# Filter6.net
KiCad netlist of a schematic drawn in Altium Designer
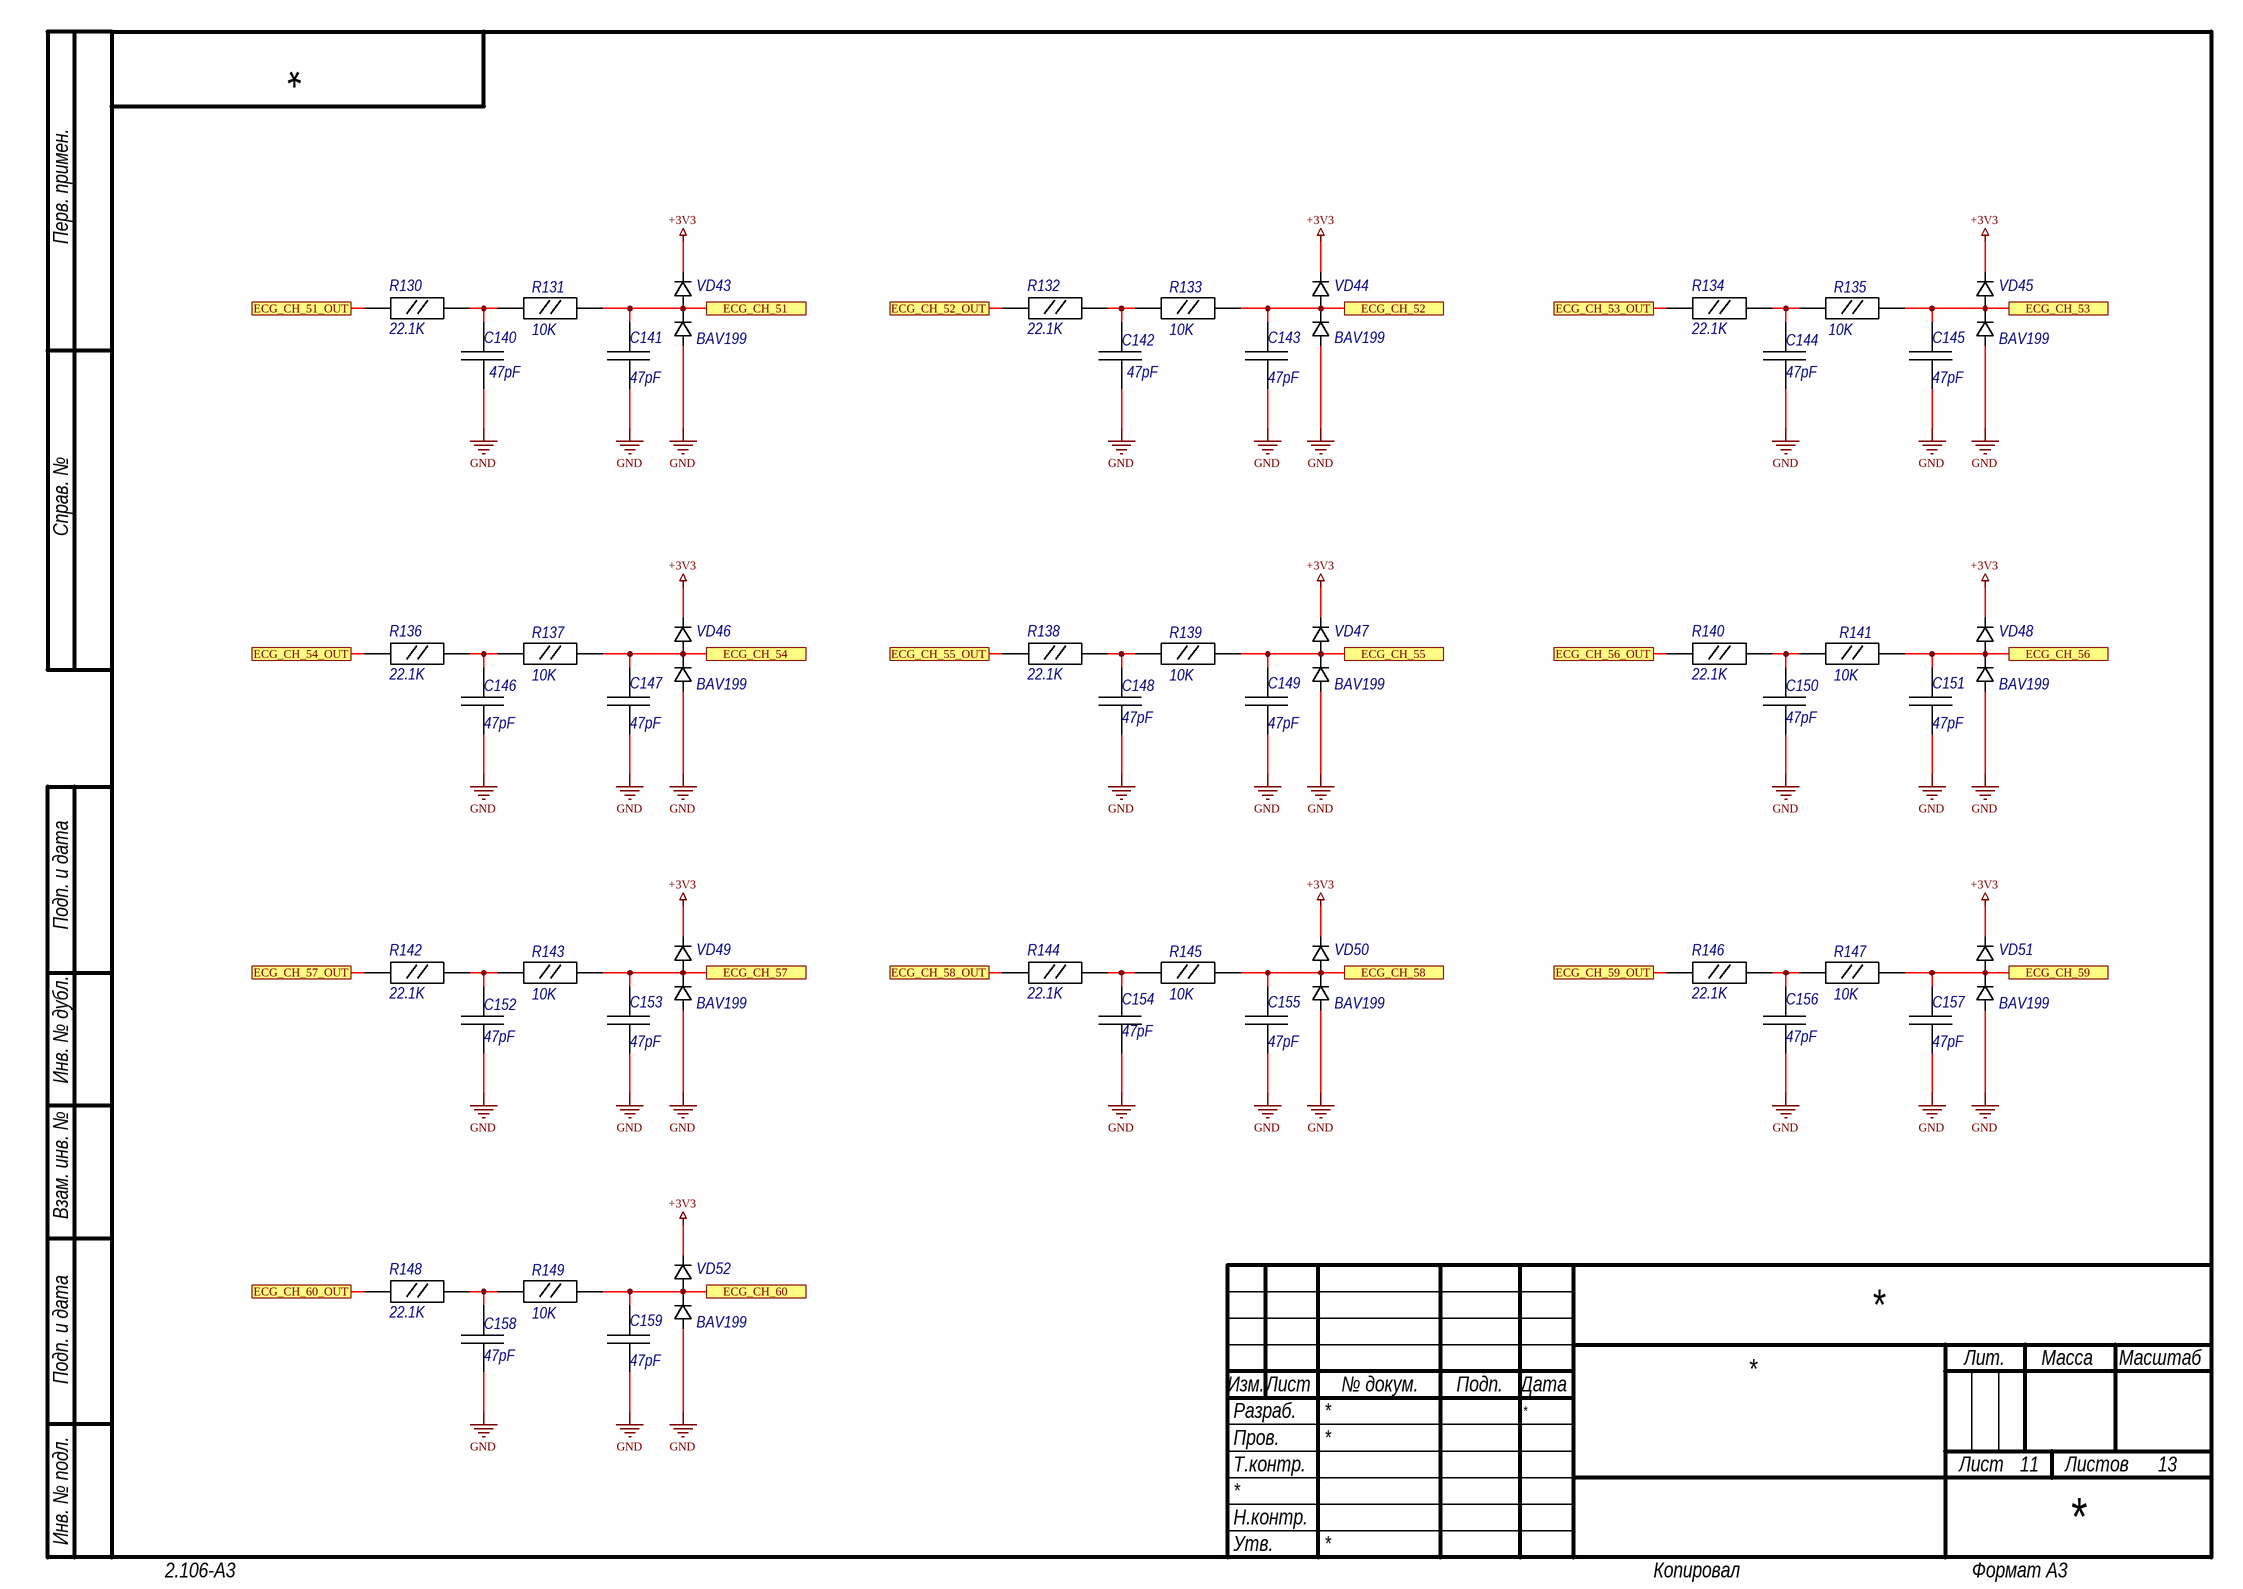
[diagram p0: Filter6.SchDoc]

(export (version "E")
  (design (tool "Eeschema 10.0.6"))
  (components
    (comp (ref "C140")
      (value "47pF")
      (footprint "C0603")
      (description "Ceramic Capacitor SMD")
      (libsource (lib "GOST") (part "CC_SMD_0603"))
    )
    (comp (ref "C141")
      (value "47pF")
      (footprint "C0603")
      (description "Ceramic Capacitor SMD")
      (libsource (lib "GOST") (part "CC_SMD_0603"))
    )
    (comp (ref "C142")
      (value "47pF")
      (footprint "C0603")
      (description "Ceramic Capacitor SMD")
      (libsource (lib "GOST") (part "CC_SMD_0603"))
    )
    (comp (ref "C143")
      (value "47pF")
      (footprint "C0603")
      (description "Ceramic Capacitor SMD")
      (libsource (lib "GOST") (part "CC_SMD_0603"))
    )
    (comp (ref "C144")
      (value "47pF")
      (footprint "C0603")
      (description "Ceramic Capacitor SMD")
      (libsource (lib "GOST") (part "CC_SMD_0603"))
    )
    (comp (ref "C145")
      (value "47pF")
      (footprint "C0603")
      (description "Ceramic Capacitor SMD")
      (libsource (lib "GOST") (part "CC_SMD_0603"))
    )
    (comp (ref "C146")
      (value "47pF")
      (footprint "C0603")
      (description "Ceramic Capacitor SMD")
      (libsource (lib "GOST") (part "CC_SMD_0603"))
    )
    (comp (ref "C147")
      (value "47pF")
      (footprint "C0603")
      (description "Ceramic Capacitor SMD")
      (libsource (lib "GOST") (part "CC_SMD_0603"))
    )
    (comp (ref "C148")
      (value "47pF")
      (footprint "C0603")
      (description "Ceramic Capacitor SMD")
      (libsource (lib "GOST") (part "CC_SMD_0603"))
    )
    (comp (ref "C149")
      (value "47pF")
      (footprint "C0603")
      (description "Ceramic Capacitor SMD")
      (libsource (lib "GOST") (part "CC_SMD_0603"))
    )
    (comp (ref "C150")
      (value "47pF")
      (footprint "C0603")
      (description "Ceramic Capacitor SMD")
      (libsource (lib "GOST") (part "CC_SMD_0603"))
    )
    (comp (ref "C151")
      (value "47pF")
      (footprint "C0603")
      (description "Ceramic Capacitor SMD")
      (libsource (lib "GOST") (part "CC_SMD_0603"))
    )
    (comp (ref "C152")
      (value "47pF")
      (footprint "C0603")
      (description "Ceramic Capacitor SMD")
      (libsource (lib "GOST") (part "CC_SMD_0603"))
    )
    (comp (ref "C153")
      (value "47pF")
      (footprint "C0603")
      (description "Ceramic Capacitor SMD")
      (libsource (lib "GOST") (part "CC_SMD_0603"))
    )
    (comp (ref "C154")
      (value "47pF")
      (footprint "C0603")
      (description "Ceramic Capacitor SMD")
      (libsource (lib "GOST") (part "CC_SMD_0603"))
    )
    (comp (ref "C155")
      (value "47pF")
      (footprint "C0603")
      (description "Ceramic Capacitor SMD")
      (libsource (lib "GOST") (part "CC_SMD_0603"))
    )
    (comp (ref "C156")
      (value "47pF")
      (footprint "C0603")
      (description "Ceramic Capacitor SMD")
      (libsource (lib "GOST") (part "CC_SMD_0603"))
    )
    (comp (ref "C157")
      (value "47pF")
      (footprint "C0603")
      (description "Ceramic Capacitor SMD")
      (libsource (lib "GOST") (part "CC_SMD_0603"))
    )
    (comp (ref "C158")
      (value "47pF")
      (footprint "C0603")
      (description "Ceramic Capacitor SMD")
      (libsource (lib "GOST") (part "CC_SMD_0603"))
    )
    (comp (ref "C159")
      (value "47pF")
      (footprint "C0603")
      (description "Ceramic Capacitor SMD")
      (libsource (lib "GOST") (part "CC_SMD_0603"))
    )
    (comp (ref "R130")
      (value "22.1K")
      (footprint "R0603")
      (description "Resistor SMD")
      (libsource (lib "GOST") (part "R0603"))
    )
    (comp (ref "R131")
      (value "10K")
      (footprint "R0603")
      (description "Resistor SMD")
      (libsource (lib "GOST") (part "R0603"))
    )
    (comp (ref "R132")
      (value "22.1K")
      (footprint "R0603")
      (description "Resistor SMD")
      (libsource (lib "GOST") (part "R0603"))
    )
    (comp (ref "R133")
      (value "10K")
      (footprint "R0603")
      (description "Resistor SMD")
      (libsource (lib "GOST") (part "R0603"))
    )
    (comp (ref "R134")
      (value "22.1K")
      (footprint "R0603")
      (description "Resistor SMD")
      (libsource (lib "GOST") (part "R0603"))
    )
    (comp (ref "R135")
      (value "10K")
      (footprint "R0603")
      (description "Resistor SMD")
      (libsource (lib "GOST") (part "R0603"))
    )
    (comp (ref "R136")
      (value "22.1K")
      (footprint "R0603")
      (description "Resistor SMD")
      (libsource (lib "GOST") (part "R0603"))
    )
    (comp (ref "R137")
      (value "10K")
      (footprint "R0603")
      (description "Resistor SMD")
      (libsource (lib "GOST") (part "R0603"))
    )
    (comp (ref "R138")
      (value "22.1K")
      (footprint "R0603")
      (description "Resistor SMD")
      (libsource (lib "GOST") (part "R0603"))
    )
    (comp (ref "R139")
      (value "10K")
      (footprint "R0603")
      (description "Resistor SMD")
      (libsource (lib "GOST") (part "R0603"))
    )
    (comp (ref "R140")
      (value "22.1K")
      (footprint "R0603")
      (description "Resistor SMD")
      (libsource (lib "GOST") (part "R0603"))
    )
    (comp (ref "R141")
      (value "10K")
      (footprint "R0603")
      (description "Resistor SMD")
      (libsource (lib "GOST") (part "R0603"))
    )
    (comp (ref "R142")
      (value "22.1K")
      (footprint "R0603")
      (description "Resistor SMD")
      (libsource (lib "GOST") (part "R0603"))
    )
    (comp (ref "R143")
      (value "10K")
      (footprint "R0603")
      (description "Resistor SMD")
      (libsource (lib "GOST") (part "R0603"))
    )
    (comp (ref "R144")
      (value "22.1K")
      (footprint "R0603")
      (description "Resistor SMD")
      (libsource (lib "GOST") (part "R0603"))
    )
    (comp (ref "R145")
      (value "10K")
      (footprint "R0603")
      (description "Resistor SMD")
      (libsource (lib "GOST") (part "R0603"))
    )
    (comp (ref "R146")
      (value "22.1K")
      (footprint "R0603")
      (description "Resistor SMD")
      (libsource (lib "GOST") (part "R0603"))
    )
    (comp (ref "R147")
      (value "10K")
      (footprint "R0603")
      (description "Resistor SMD")
      (libsource (lib "GOST") (part "R0603"))
    )
    (comp (ref "R148")
      (value "22.1K")
      (footprint "R0603")
      (description "Resistor SMD")
      (libsource (lib "GOST") (part "R0603"))
    )
    (comp (ref "R149")
      (value "10K")
      (footprint "R0603")
      (description "Resistor SMD")
      (libsource (lib "GOST") (part "R0603"))
    )
    (comp (ref "VD43")
      (value "BAV199")
      (footprint "SOT23")
      (description "Diod Schottky")
      (fields (field (name "MANUFACTURER PART NUMBER 1") "BAV199"))
      (libsource (lib "GOST") (part "DIODE_BAV199"))
    )
    (comp (ref "VD44")
      (value "BAV199")
      (footprint "SOT23")
      (description "Diod Schottky")
      (fields (field (name "MANUFACTURER PART NUMBER 1") "BAV199"))
      (libsource (lib "GOST") (part "DIODE_BAV199"))
    )
    (comp (ref "VD45")
      (value "BAV199")
      (footprint "SOT23")
      (description "Diod Schottky")
      (fields (field (name "MANUFACTURER PART NUMBER 1") "BAV199"))
      (libsource (lib "GOST") (part "DIODE_BAV199"))
    )
    (comp (ref "VD46")
      (value "BAV199")
      (footprint "SOT23")
      (description "Diod Schottky")
      (fields (field (name "MANUFACTURER PART NUMBER 1") "BAV199"))
      (libsource (lib "GOST") (part "DIODE_BAV199"))
    )
    (comp (ref "VD47")
      (value "BAV199")
      (footprint "SOT23")
      (description "Diod Schottky")
      (fields (field (name "MANUFACTURER PART NUMBER 1") "BAV199"))
      (libsource (lib "GOST") (part "DIODE_BAV199"))
    )
    (comp (ref "VD48")
      (value "BAV199")
      (footprint "SOT23")
      (description "Diod Schottky")
      (fields (field (name "MANUFACTURER PART NUMBER 1") "BAV199"))
      (libsource (lib "GOST") (part "DIODE_BAV199"))
    )
    (comp (ref "VD49")
      (value "BAV199")
      (footprint "SOT23")
      (description "Diod Schottky")
      (fields (field (name "MANUFACTURER PART NUMBER 1") "BAV199"))
      (libsource (lib "GOST") (part "DIODE_BAV199"))
    )
    (comp (ref "VD50")
      (value "BAV199")
      (footprint "SOT23")
      (description "Diod Schottky")
      (fields (field (name "MANUFACTURER PART NUMBER 1") "BAV199"))
      (libsource (lib "GOST") (part "DIODE_BAV199"))
    )
    (comp (ref "VD51")
      (value "BAV199")
      (footprint "SOT23")
      (description "Diod Schottky")
      (fields (field (name "MANUFACTURER PART NUMBER 1") "BAV199"))
      (libsource (lib "GOST") (part "DIODE_BAV199"))
    )
    (comp (ref "VD52")
      (value "BAV199")
      (footprint "SOT23")
      (description "Diod Schottky")
      (fields (field (name "MANUFACTURER PART NUMBER 1") "BAV199"))
      (libsource (lib "GOST") (part "DIODE_BAV199"))
    )
  )
  (nets
    (net (code "1") (name "+3V3") (class "Default")
      (node (ref "VD43") (pin "2") (pinfunction "2_2") (pintype "passive"))
      (node (ref "VD44") (pin "2") (pinfunction "2_2") (pintype "passive"))
      (node (ref "VD45") (pin "2") (pinfunction "2_2") (pintype "passive"))
      (node (ref "VD46") (pin "2") (pinfunction "2_2") (pintype "passive"))
      (node (ref "VD47") (pin "2") (pinfunction "2_2") (pintype "passive"))
      (node (ref "VD48") (pin "2") (pinfunction "2_2") (pintype "passive"))
      (node (ref "VD49") (pin "2") (pinfunction "2_2") (pintype "passive"))
      (node (ref "VD50") (pin "2") (pinfunction "2_2") (pintype "passive"))
      (node (ref "VD51") (pin "2") (pinfunction "2_2") (pintype "passive"))
      (node (ref "VD52") (pin "2") (pinfunction "2_2") (pintype "passive"))
    )
    (net (code "2") (name "/ECG_CH_51") (class "Default")
      (node (ref "C141") (pin "2") (pinfunction "2_2") (pintype "passive"))
      (node (ref "R131") (pin "2") (pinfunction "2_2") (pintype "passive"))
      (node (ref "VD43") (pin "3") (pinfunction "3_3") (pintype "passive"))
    )
    (net (code "3") (name "/ECG_CH_51_OUT") (class "Default")
      (node (ref "R130") (pin "1") (pinfunction "1_1") (pintype "passive"))
    )
    (net (code "4") (name "/ECG_CH_52") (class "Default")
      (node (ref "C143") (pin "2") (pinfunction "2_2") (pintype "passive"))
      (node (ref "R133") (pin "2") (pinfunction "2_2") (pintype "passive"))
      (node (ref "VD44") (pin "3") (pinfunction "3_3") (pintype "passive"))
    )
    (net (code "5") (name "/ECG_CH_52_OUT") (class "Default")
      (node (ref "R132") (pin "1") (pinfunction "1_1") (pintype "passive"))
    )
    (net (code "6") (name "/ECG_CH_53") (class "Default")
      (node (ref "C145") (pin "2") (pinfunction "2_2") (pintype "passive"))
      (node (ref "R135") (pin "2") (pinfunction "2_2") (pintype "passive"))
      (node (ref "VD45") (pin "3") (pinfunction "3_3") (pintype "passive"))
    )
    (net (code "7") (name "/ECG_CH_53_OUT") (class "Default")
      (node (ref "R134") (pin "1") (pinfunction "1_1") (pintype "passive"))
    )
    (net (code "8") (name "/ECG_CH_54") (class "Default")
      (node (ref "C147") (pin "2") (pinfunction "2_2") (pintype "passive"))
      (node (ref "R137") (pin "2") (pinfunction "2_2") (pintype "passive"))
      (node (ref "VD46") (pin "3") (pinfunction "3_3") (pintype "passive"))
    )
    (net (code "9") (name "/ECG_CH_54_OUT") (class "Default")
      (node (ref "R136") (pin "1") (pinfunction "1_1") (pintype "passive"))
    )
    (net (code "10") (name "/ECG_CH_55") (class "Default")
      (node (ref "C149") (pin "2") (pinfunction "2_2") (pintype "passive"))
      (node (ref "R139") (pin "2") (pinfunction "2_2") (pintype "passive"))
      (node (ref "VD47") (pin "3") (pinfunction "3_3") (pintype "passive"))
    )
    (net (code "11") (name "/ECG_CH_55_OUT") (class "Default")
      (node (ref "R138") (pin "1") (pinfunction "1_1") (pintype "passive"))
    )
    (net (code "12") (name "/ECG_CH_56") (class "Default")
      (node (ref "C151") (pin "2") (pinfunction "2_2") (pintype "passive"))
      (node (ref "R141") (pin "2") (pinfunction "2_2") (pintype "passive"))
      (node (ref "VD48") (pin "3") (pinfunction "3_3") (pintype "passive"))
    )
    (net (code "13") (name "/ECG_CH_56_OUT") (class "Default")
      (node (ref "R140") (pin "1") (pinfunction "1_1") (pintype "passive"))
    )
    (net (code "14") (name "/ECG_CH_57") (class "Default")
      (node (ref "C153") (pin "2") (pinfunction "2_2") (pintype "passive"))
      (node (ref "R143") (pin "2") (pinfunction "2_2") (pintype "passive"))
      (node (ref "VD49") (pin "3") (pinfunction "3_3") (pintype "passive"))
    )
    (net (code "15") (name "/ECG_CH_57_OUT") (class "Default")
      (node (ref "R142") (pin "1") (pinfunction "1_1") (pintype "passive"))
    )
    (net (code "16") (name "/ECG_CH_58") (class "Default")
      (node (ref "C155") (pin "2") (pinfunction "2_2") (pintype "passive"))
      (node (ref "R145") (pin "2") (pinfunction "2_2") (pintype "passive"))
      (node (ref "VD50") (pin "3") (pinfunction "3_3") (pintype "passive"))
    )
    (net (code "17") (name "/ECG_CH_58_OUT") (class "Default")
      (node (ref "R144") (pin "1") (pinfunction "1_1") (pintype "passive"))
    )
    (net (code "18") (name "/ECG_CH_59") (class "Default")
      (node (ref "C157") (pin "2") (pinfunction "2_2") (pintype "passive"))
      (node (ref "R147") (pin "2") (pinfunction "2_2") (pintype "passive"))
      (node (ref "VD51") (pin "3") (pinfunction "3_3") (pintype "passive"))
    )
    (net (code "19") (name "/ECG_CH_59_OUT") (class "Default")
      (node (ref "R146") (pin "1") (pinfunction "1_1") (pintype "passive"))
    )
    (net (code "20") (name "/ECG_CH_60") (class "Default")
      (node (ref "C159") (pin "2") (pinfunction "2_2") (pintype "passive"))
      (node (ref "R149") (pin "2") (pinfunction "2_2") (pintype "passive"))
      (node (ref "VD52") (pin "3") (pinfunction "3_3") (pintype "passive"))
    )
    (net (code "21") (name "/ECG_CH_60_OUT") (class "Default")
      (node (ref "R148") (pin "1") (pinfunction "1_1") (pintype "passive"))
    )
    (net (code "22") (name "GND") (class "Default")
      (node (ref "C140") (pin "1") (pinfunction "1_1") (pintype "passive"))
      (node (ref "C141") (pin "1") (pinfunction "1_1") (pintype "passive"))
      (node (ref "C142") (pin "1") (pinfunction "1_1") (pintype "passive"))
      (node (ref "C143") (pin "1") (pinfunction "1_1") (pintype "passive"))
      (node (ref "C144") (pin "1") (pinfunction "1_1") (pintype "passive"))
      (node (ref "C145") (pin "1") (pinfunction "1_1") (pintype "passive"))
      (node (ref "C146") (pin "1") (pinfunction "1_1") (pintype "passive"))
      (node (ref "C147") (pin "1") (pinfunction "1_1") (pintype "passive"))
      (node (ref "C148") (pin "1") (pinfunction "1_1") (pintype "passive"))
      (node (ref "C149") (pin "1") (pinfunction "1_1") (pintype "passive"))
      (node (ref "C150") (pin "1") (pinfunction "1_1") (pintype "passive"))
      (node (ref "C151") (pin "1") (pinfunction "1_1") (pintype "passive"))
      (node (ref "C152") (pin "1") (pinfunction "1_1") (pintype "passive"))
      (node (ref "C153") (pin "1") (pinfunction "1_1") (pintype "passive"))
      (node (ref "C154") (pin "1") (pinfunction "1_1") (pintype "passive"))
      (node (ref "C155") (pin "1") (pinfunction "1_1") (pintype "passive"))
      (node (ref "C156") (pin "1") (pinfunction "1_1") (pintype "passive"))
      (node (ref "C157") (pin "1") (pinfunction "1_1") (pintype "passive"))
      (node (ref "C158") (pin "1") (pinfunction "1_1") (pintype "passive"))
      (node (ref "C159") (pin "1") (pinfunction "1_1") (pintype "passive"))
      (node (ref "VD43") (pin "1") (pinfunction "1_1") (pintype "passive"))
      (node (ref "VD44") (pin "1") (pinfunction "1_1") (pintype "passive"))
      (node (ref "VD45") (pin "1") (pinfunction "1_1") (pintype "passive"))
      (node (ref "VD46") (pin "1") (pinfunction "1_1") (pintype "passive"))
      (node (ref "VD47") (pin "1") (pinfunction "1_1") (pintype "passive"))
      (node (ref "VD48") (pin "1") (pinfunction "1_1") (pintype "passive"))
      (node (ref "VD49") (pin "1") (pinfunction "1_1") (pintype "passive"))
      (node (ref "VD50") (pin "1") (pinfunction "1_1") (pintype "passive"))
      (node (ref "VD51") (pin "1") (pinfunction "1_1") (pintype "passive"))
      (node (ref "VD52") (pin "1") (pinfunction "1_1") (pintype "passive"))
    )
    (net (code "23") (name "Net-(C140-Pad2)") (class "Default")
      (node (ref "C140") (pin "2") (pinfunction "2_2") (pintype "passive"))
      (node (ref "R130") (pin "2") (pinfunction "2_2") (pintype "passive"))
      (node (ref "R131") (pin "1") (pinfunction "1_1") (pintype "passive"))
    )
    (net (code "24") (name "Net-(C142-Pad2)") (class "Default")
      (node (ref "C142") (pin "2") (pinfunction "2_2") (pintype "passive"))
      (node (ref "R132") (pin "2") (pinfunction "2_2") (pintype "passive"))
      (node (ref "R133") (pin "1") (pinfunction "1_1") (pintype "passive"))
    )
    (net (code "25") (name "Net-(C144-Pad2)") (class "Default")
      (node (ref "C144") (pin "2") (pinfunction "2_2") (pintype "passive"))
      (node (ref "R134") (pin "2") (pinfunction "2_2") (pintype "passive"))
      (node (ref "R135") (pin "1") (pinfunction "1_1") (pintype "passive"))
    )
    (net (code "26") (name "Net-(C146-Pad2)") (class "Default")
      (node (ref "C146") (pin "2") (pinfunction "2_2") (pintype "passive"))
      (node (ref "R136") (pin "2") (pinfunction "2_2") (pintype "passive"))
      (node (ref "R137") (pin "1") (pinfunction "1_1") (pintype "passive"))
    )
    (net (code "27") (name "Net-(C148-Pad2)") (class "Default")
      (node (ref "C148") (pin "2") (pinfunction "2_2") (pintype "passive"))
      (node (ref "R138") (pin "2") (pinfunction "2_2") (pintype "passive"))
      (node (ref "R139") (pin "1") (pinfunction "1_1") (pintype "passive"))
    )
    (net (code "28") (name "Net-(C150-Pad2)") (class "Default")
      (node (ref "C150") (pin "2") (pinfunction "2_2") (pintype "passive"))
      (node (ref "R140") (pin "2") (pinfunction "2_2") (pintype "passive"))
      (node (ref "R141") (pin "1") (pinfunction "1_1") (pintype "passive"))
    )
    (net (code "29") (name "Net-(C152-Pad2)") (class "Default")
      (node (ref "C152") (pin "2") (pinfunction "2_2") (pintype "passive"))
      (node (ref "R142") (pin "2") (pinfunction "2_2") (pintype "passive"))
      (node (ref "R143") (pin "1") (pinfunction "1_1") (pintype "passive"))
    )
    (net (code "30") (name "Net-(C154-Pad2)") (class "Default")
      (node (ref "C154") (pin "2") (pinfunction "2_2") (pintype "passive"))
      (node (ref "R144") (pin "2") (pinfunction "2_2") (pintype "passive"))
      (node (ref "R145") (pin "1") (pinfunction "1_1") (pintype "passive"))
    )
    (net (code "31") (name "Net-(C156-Pad2)") (class "Default")
      (node (ref "C156") (pin "2") (pinfunction "2_2") (pintype "passive"))
      (node (ref "R146") (pin "2") (pinfunction "2_2") (pintype "passive"))
      (node (ref "R147") (pin "1") (pinfunction "1_1") (pintype "passive"))
    )
    (net (code "32") (name "Net-(C158-Pad2)") (class "Default")
      (node (ref "C158") (pin "2") (pinfunction "2_2") (pintype "passive"))
      (node (ref "R148") (pin "2") (pinfunction "2_2") (pintype "passive"))
      (node (ref "R149") (pin "1") (pinfunction "1_1") (pintype "passive"))
    )
  )
)
